# SCH_Controller_EasyEDA.net
KiCad netlist of a schematic drawn in EasyEDA
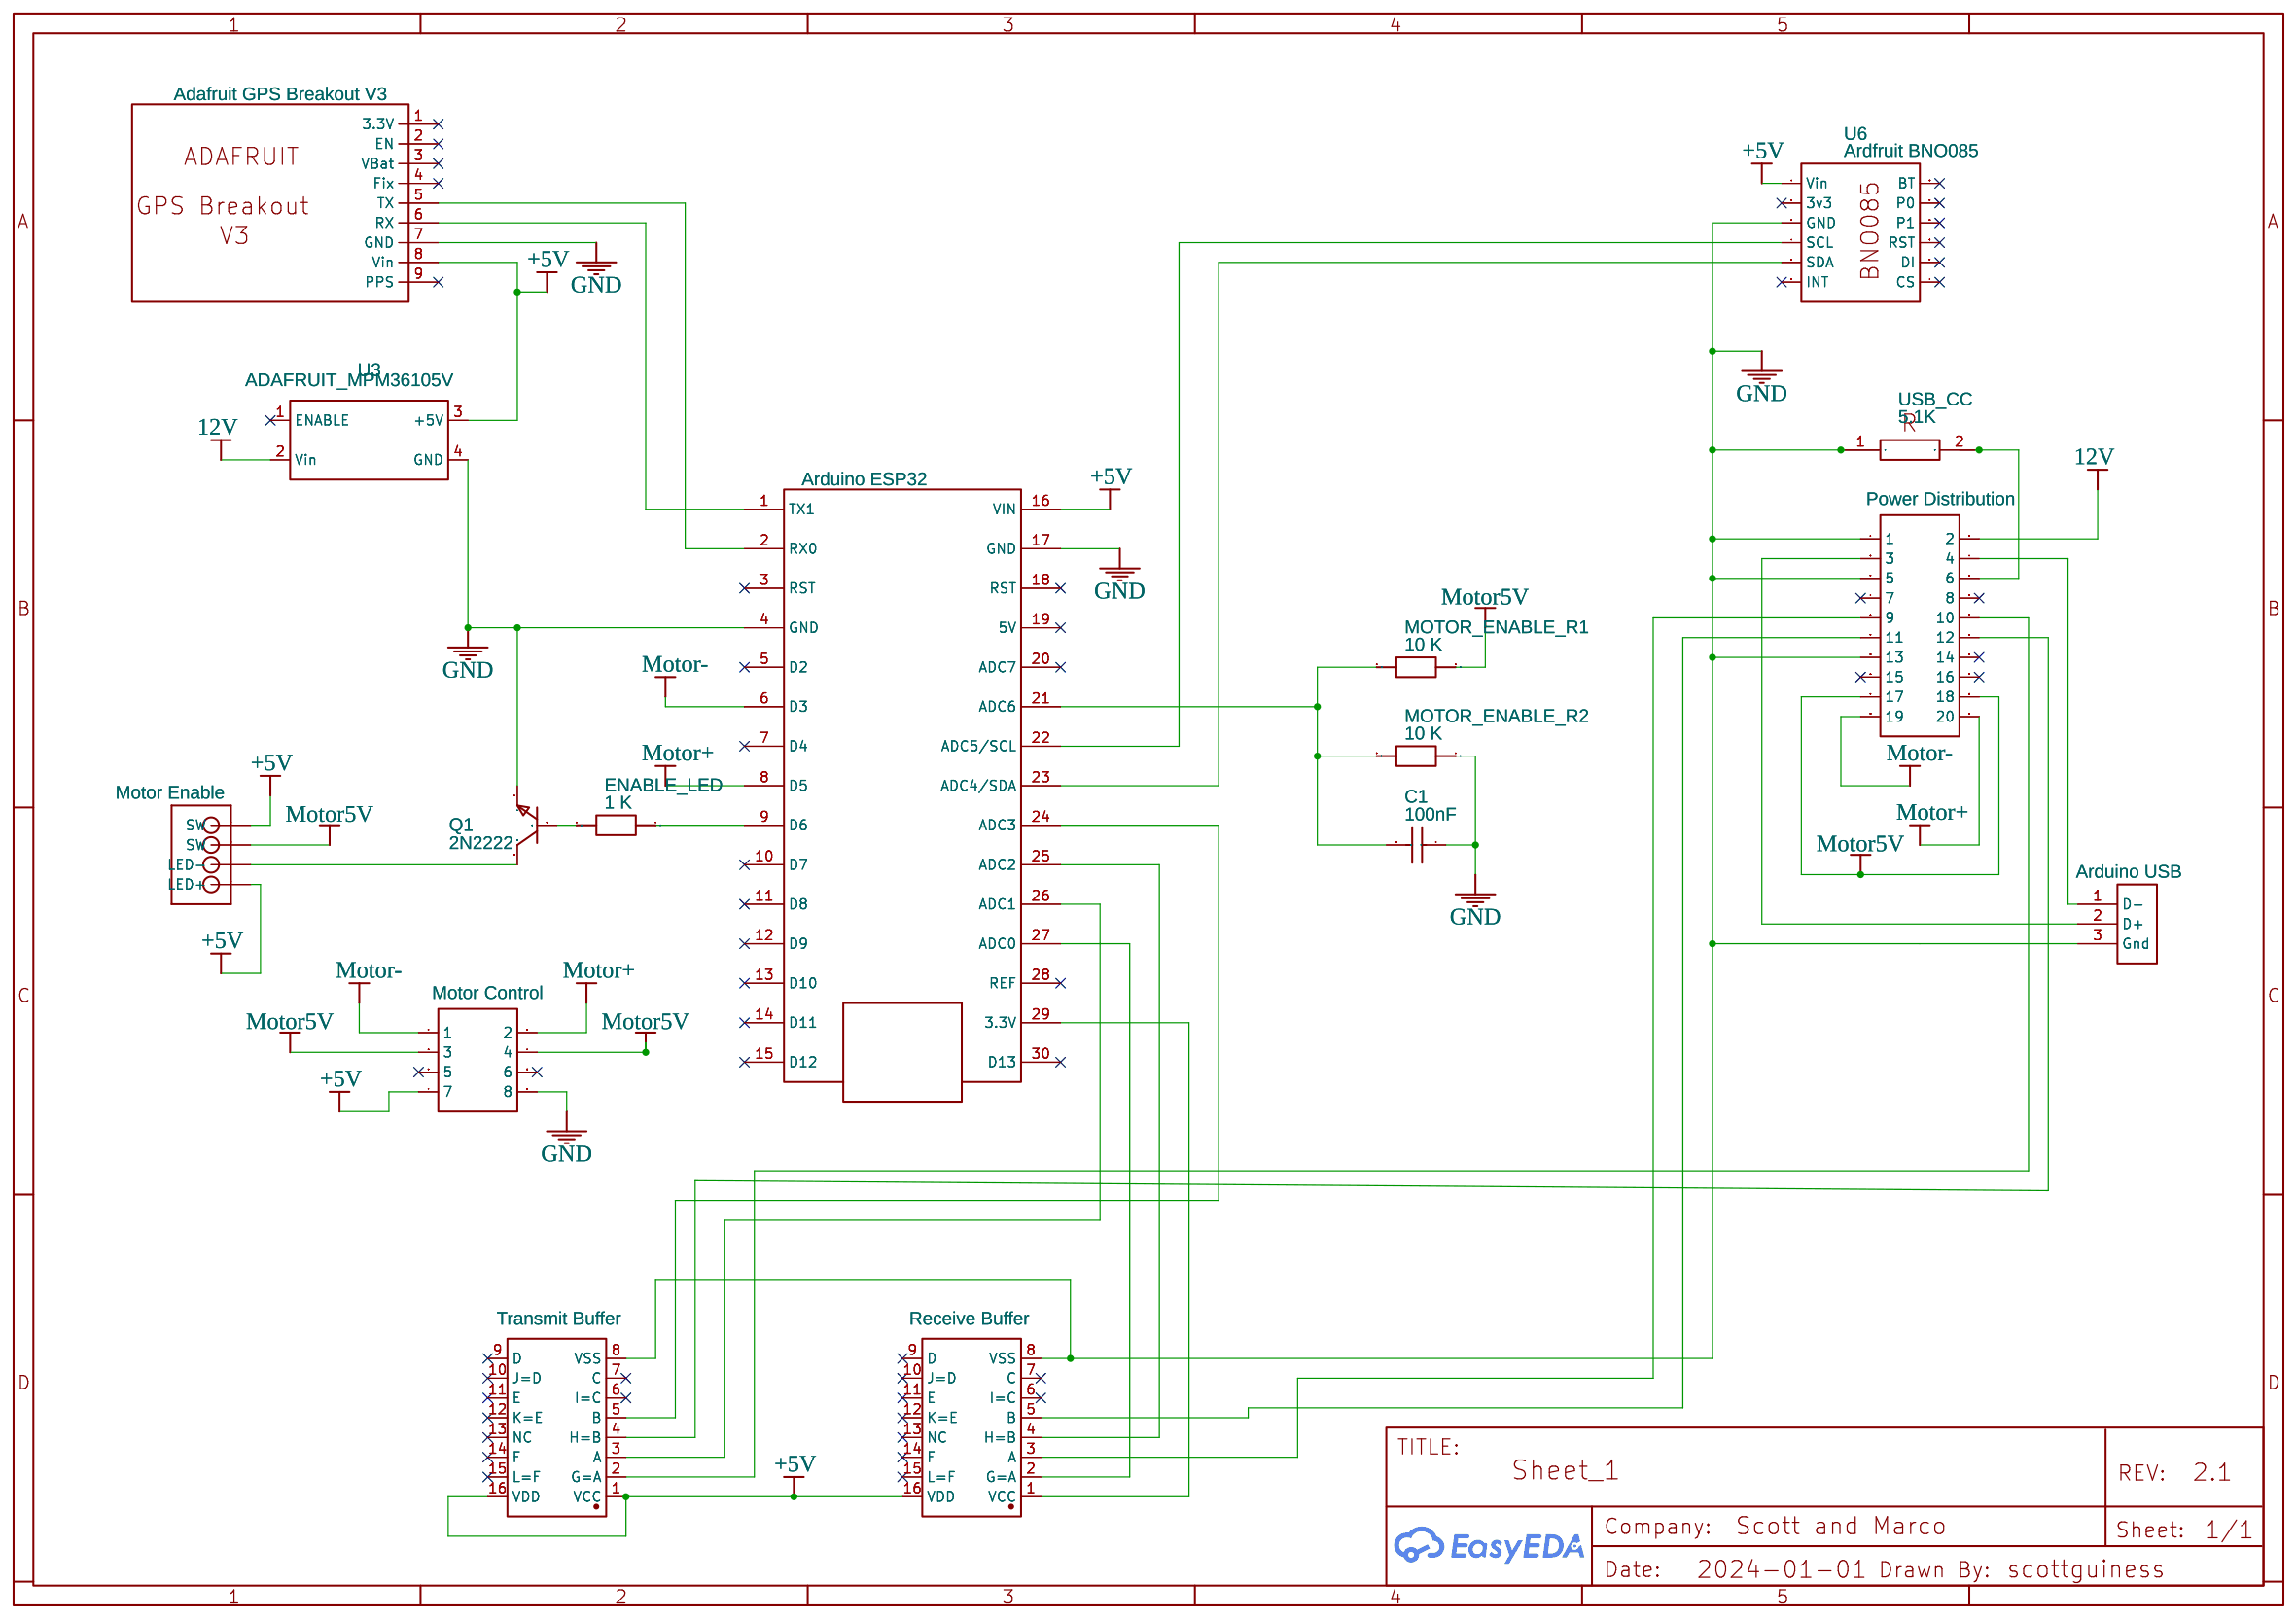
[diagram p0: schematic sheet]

(export (version "E")
  (design (tool "Eeschema 10.0.6"))
  (components
    (comp (ref "C1")
      (value "100nF")
      (fields (field (name "Manufacturer Part") "Capacitor_Ceramic"))
      (libsource (lib "") (part "Capacitor_Ceramic"))
    )
    (comp (ref "ENABLE_LED") (value "1 K") (libsource (lib "") (part "1 K 0.25w_1")))
    (comp (ref "HDR-M-2.54_2X4") (value "Motor Control") (libsource (lib "") (part "HDR-M-2.54_2x4")))
    (comp (ref "JST_XH_1X3") (value "Arduino USB") (libsource (lib "") (part "JST XH 1x3")))
    (comp (ref "MOTOR_ENABLE_R1") (value "10 K") (libsource (lib "") (part "1 K 0.25w")))
    (comp (ref "MOTOR_ENABLE_R2") (value "10 K") (libsource (lib "") (part "1 K 0.25w")))
    (comp (ref "POWER1") (value "Power Distribution") (libsource (lib "") (part "HDR-M-2.54_2x10")))
    (comp (ref "Q1")
      (value "2N2222")
      (fields (field (name "Manufacturer Part") "2N2222A") (field (name "Manufacturer") "ST(先科)"))
      (libsource (lib "") (part "2N2222"))
    )
    (comp (ref "U1") (value "Arduino ESP32") (libsource (lib "") (part "ARDUINO_NANO_R3")))
    (comp (ref "U2")
      (value "Receive Buffer")
      (fields (field (name "Manufacturer Part") "CD4010BE") (field (name "Manufacturer") "TI(德州仪器)"))
      (libsource (lib "") (part "CD4010BE"))
    )
    (comp (ref "U3") (value "ADAFRUIT_MPM36105V") (libsource (lib "") (part "ADAFRUIT_MPM36105V")))
    (comp (ref "U4")
      (value "Adafruit GPS Breakout V3")
      (fields (field (name "Manufacturer Part") "New SchematicLib"))
      (libsource (lib "") (part "Adafruit GPS Breakout V3"))
    )
    (comp (ref "U5")
      (value "Transmit Buffer")
      (fields (field (name "Manufacturer Part") "CD4010BE") (field (name "Manufacturer") "TI(德州仪器)"))
      (libsource (lib "") (part "CD4010BE"))
    )
    (comp (ref "U6")
      (value "Ardfruit BNO085")
      (fields (field (name "Manufacturer") "Ardfruit"))
      (libsource (lib "") (part "Ardfruit BNO085"))
    )
    (comp (ref "U7") (value "Motor Enable") (libsource (lib "") (part "HEADER-1X4-2.54-JST-PH")))
    (comp (ref "USB_CC")
      (value "5.1K")
      (fields (field (name "Manufacturer Part") "4211R-13") (field (name "Manufacturer") "API Delevan"))
      (libsource (lib "") (part "0.5W Resistor"))
    )
  )
  (nets
    (net (code "1") (name "+5V") (class "Default")
      (node (ref "HDR-M-2.54_2X4") (pin "7") (pinfunction "7_7") (pintype "unspecified"))
      (node (ref "U1") (pin "16") (pinfunction "VIN_16") (pintype "unspecified"))
      (node (ref "U2") (pin "16") (pinfunction "VDD_16") (pintype "unspecified"))
      (node (ref "U3") (pin "3") (pinfunction "+5V_3") (pintype "unspecified"))
      (node (ref "U4") (pin "8") (pinfunction "Vin_8") (pintype "unspecified"))
      (node (ref "U5") (pin "1") (pinfunction "VCC_1") (pintype "unspecified"))
      (node (ref "U5") (pin "16") (pinfunction "VDD_16") (pintype "unspecified"))
      (node (ref "U6") (pin "1") (pinfunction "Vin_1") (pintype "unspecified"))
      (node (ref "U7") (pin "P1") (pinfunction "SW_P1") (pintype "unspecified"))
      (node (ref "U7") (pin "P4") (pinfunction "LED+_P4") (pintype "unspecified"))
    )
    (net (code "2") (name "12V") (class "Default")
      (node (ref "POWER1") (pin "2") (pinfunction "2_2") (pintype "unspecified"))
      (node (ref "U3") (pin "2") (pinfunction "Vin_2") (pintype "unspecified"))
    )
    (net (code "3") (name "GND") (class "Default")
      (node (ref "C1") (pin "1") (pinfunction "1_1") (pintype "unspecified"))
      (node (ref "HDR-M-2.54_2X4") (pin "8") (pinfunction "8_8") (pintype "unspecified"))
      (node (ref "JST_XH_1X3") (pin "3") (pinfunction "Gnd_3") (pintype "unspecified"))
      (node (ref "MOTOR_ENABLE_R2") (pin "1") (pinfunction "1_1") (pintype "unspecified"))
      (node (ref "POWER1") (pin "1") (pinfunction "1_1") (pintype "unspecified"))
      (node (ref "POWER1") (pin "13") (pinfunction "13_13") (pintype "unspecified"))
      (node (ref "POWER1") (pin "5") (pinfunction "5_5") (pintype "unspecified"))
      (node (ref "Q1") (pin "1") (pinfunction "E_1") (pintype "unspecified"))
      (node (ref "U1") (pin "17") (pinfunction "GND_17") (pintype "unspecified"))
      (node (ref "U1") (pin "4") (pinfunction "GND_4") (pintype "unspecified"))
      (node (ref "U2") (pin "8") (pinfunction "VSS_8") (pintype "unspecified"))
      (node (ref "U3") (pin "4") (pinfunction "GND_4") (pintype "unspecified"))
      (node (ref "U4") (pin "7") (pinfunction "GND_7") (pintype "unspecified"))
      (node (ref "U5") (pin "8") (pinfunction "VSS_8") (pintype "unspecified"))
      (node (ref "U6") (pin "3") (pinfunction "GND_3") (pintype "unspecified"))
      (node (ref "USB_CC") (pin "1") (pinfunction "1_1") (pintype "unspecified"))
    )
    (net (code "4") (name "Motor+") (class "Default")
      (node (ref "HDR-M-2.54_2X4") (pin "2") (pinfunction "2_2") (pintype "unspecified"))
      (node (ref "POWER1") (pin "20") (pinfunction "20_20") (pintype "unspecified"))
      (node (ref "U1") (pin "8") (pinfunction "D5_8") (pintype "unspecified"))
    )
    (net (code "5") (name "Motor-") (class "Default")
      (node (ref "HDR-M-2.54_2X4") (pin "1") (pinfunction "1_1") (pintype "unspecified"))
      (node (ref "POWER1") (pin "19") (pinfunction "19_19") (pintype "unspecified"))
      (node (ref "U1") (pin "6") (pinfunction "D3_6") (pintype "unspecified"))
    )
    (net (code "6") (name "Motor5V") (class "Default")
      (node (ref "HDR-M-2.54_2X4") (pin "3") (pinfunction "3_3") (pintype "unspecified"))
      (node (ref "HDR-M-2.54_2X4") (pin "4") (pinfunction "4_4") (pintype "unspecified"))
      (node (ref "MOTOR_ENABLE_R1") (pin "1") (pinfunction "1_1") (pintype "unspecified"))
      (node (ref "POWER1") (pin "17") (pinfunction "17_17") (pintype "unspecified"))
      (node (ref "POWER1") (pin "18") (pinfunction "18_18") (pintype "unspecified"))
      (node (ref "U7") (pin "P2") (pinfunction "SW_P2") (pintype "unspecified"))
    )
    (net (code "7") (name "Net-(JST_XH_1X3-D+)") (class "Default")
      (node (ref "JST_XH_1X3") (pin "2") (pinfunction "D+_2") (pintype "unspecified"))
      (node (ref "POWER1") (pin "3") (pinfunction "3_3") (pintype "unspecified"))
    )
    (net (code "8") (name "Net-(JST_XH_1X3-D-)") (class "Default")
      (node (ref "JST_XH_1X3") (pin "1") (pinfunction "D-_1") (pintype "unspecified"))
      (node (ref "POWER1") (pin "4") (pinfunction "4_4") (pintype "unspecified"))
    )
    (net (code "9") (name "Net-(POWER1-Pad6)") (class "Default")
      (node (ref "POWER1") (pin "6") (pinfunction "6_6") (pintype "unspecified"))
      (node (ref "USB_CC") (pin "2") (pinfunction "2_2") (pintype "unspecified"))
    )
    (net (code "10") (name "Net-(Q1-B)") (class "Default")
      (node (ref "ENABLE_LED") (pin "2") (pinfunction "2_2") (pintype "unspecified"))
      (node (ref "Q1") (pin "2") (pinfunction "B_2") (pintype "unspecified"))
    )
    (net (code "11") (name "Net-(Q1-C)") (class "Default")
      (node (ref "Q1") (pin "3") (pinfunction "C_3") (pintype "unspecified"))
      (node (ref "U7") (pin "P3") (pinfunction "LED-_P3") (pintype "unspecified"))
    )
    (net (code "12") (name "Net-(U1-3.3V)") (class "Default")
      (node (ref "U1") (pin "29") (pinfunction "3.3V_29") (pintype "unspecified"))
      (node (ref "U2") (pin "1") (pinfunction "VCC_1") (pintype "unspecified"))
    )
    (net (code "13") (name "Net-(U1-ADC0)") (class "Default")
      (node (ref "U1") (pin "27") (pinfunction "ADC0_27") (pintype "unspecified"))
      (node (ref "U2") (pin "2") (pinfunction "G=A_2") (pintype "unspecified"))
    )
    (net (code "14") (name "Net-(U1-ADC1)") (class "Default")
      (node (ref "U1") (pin "26") (pinfunction "ADC1_26") (pintype "unspecified"))
      (node (ref "U5") (pin "3") (pinfunction "A_3") (pintype "unspecified"))
    )
    (net (code "15") (name "Net-(U1-ADC2)") (class "Default")
      (node (ref "U1") (pin "25") (pinfunction "ADC2_25") (pintype "unspecified"))
      (node (ref "U2") (pin "4") (pinfunction "H=B_4") (pintype "unspecified"))
    )
    (net (code "16") (name "Net-(U1-ADC3)") (class "Default")
      (node (ref "U1") (pin "24") (pinfunction "ADC3_24") (pintype "unspecified"))
      (node (ref "U5") (pin "5") (pinfunction "B_5") (pintype "unspecified"))
    )
    (net (code "17") (name "Net-(U1-ADC4{slash}SDA)") (class "Default")
      (node (ref "U1") (pin "23") (pinfunction "ADC4/SDA_23") (pintype "unspecified"))
      (node (ref "U6") (pin "5") (pinfunction "SDA_5") (pintype "unspecified"))
    )
    (net (code "18") (name "Net-(U1-ADC5{slash}SCL)") (class "Default")
      (node (ref "U1") (pin "22") (pinfunction "ADC5/SCL_22") (pintype "unspecified"))
      (node (ref "U6") (pin "4") (pinfunction "SCL_4") (pintype "unspecified"))
    )
    (net (code "19") (name "Net-(U1-ADC6)") (class "Default")
      (node (ref "C1") (pin "2") (pinfunction "2_2") (pintype "unspecified"))
      (node (ref "MOTOR_ENABLE_R1") (pin "2") (pinfunction "2_2") (pintype "unspecified"))
      (node (ref "MOTOR_ENABLE_R2") (pin "2") (pinfunction "2_2") (pintype "unspecified"))
      (node (ref "U1") (pin "21") (pinfunction "ADC6_21") (pintype "unspecified"))
    )
    (net (code "20") (name "Net-(U1-D6)") (class "Default")
      (node (ref "ENABLE_LED") (pin "1") (pinfunction "1_1") (pintype "unspecified"))
      (node (ref "U1") (pin "9") (pinfunction "D6_9") (pintype "unspecified"))
    )
    (net (code "21") (name "Net-(U1-RX0)") (class "Default")
      (node (ref "U1") (pin "2") (pinfunction "RX0_2") (pintype "unspecified"))
      (node (ref "U4") (pin "5") (pinfunction "TX_5") (pintype "unspecified"))
    )
    (net (code "22") (name "Net-(U1-TX1)") (class "Default")
      (node (ref "U1") (pin "1") (pinfunction "TX1_1") (pintype "unspecified"))
      (node (ref "U4") (pin "6") (pinfunction "RX_6") (pintype "unspecified"))
    )
    (net (code "23") (name "Net-(U2-A)") (class "Default")
      (node (ref "POWER1") (pin "9") (pinfunction "9_9") (pintype "unspecified"))
      (node (ref "U2") (pin "3") (pinfunction "A_3") (pintype "unspecified"))
    )
    (net (code "24") (name "Net-(U2-B)") (class "Default")
      (node (ref "POWER1") (pin "11") (pinfunction "11_11") (pintype "unspecified"))
      (node (ref "U2") (pin "5") (pinfunction "B_5") (pintype "unspecified"))
    )
    (net (code "25") (name "Net-(U5-G=A)") (class "Default")
      (node (ref "POWER1") (pin "10") (pinfunction "10_10") (pintype "unspecified"))
      (node (ref "U5") (pin "2") (pinfunction "G=A_2") (pintype "unspecified"))
    )
    (net (code "26") (name "Net-(U5-H=B)") (class "Default")
      (node (ref "POWER1") (pin "12") (pinfunction "12_12") (pintype "unspecified"))
      (node (ref "U5") (pin "4") (pinfunction "H=B_4") (pintype "unspecified"))
    )
    (net (code "27") (name "unconnected-(HDR-M-2.54_2X4-Pad5)") (class "Default")
      (node (ref "HDR-M-2.54_2X4") (pin "5") (pinfunction "5_5") (pintype "unspecified+no_connect"))
    )
    (net (code "28") (name "unconnected-(HDR-M-2.54_2X4-Pad6)") (class "Default")
      (node (ref "HDR-M-2.54_2X4") (pin "6") (pinfunction "6_6") (pintype "unspecified+no_connect"))
    )
    (net (code "29") (name "unconnected-(POWER1-Pad7)") (class "Default")
      (node (ref "POWER1") (pin "7") (pinfunction "7_7") (pintype "unspecified+no_connect"))
    )
    (net (code "30") (name "unconnected-(POWER1-Pad8)") (class "Default")
      (node (ref "POWER1") (pin "8") (pinfunction "8_8") (pintype "unspecified+no_connect"))
    )
    (net (code "31") (name "unconnected-(POWER1-Pad14)") (class "Default")
      (node (ref "POWER1") (pin "14") (pinfunction "14_14") (pintype "unspecified+no_connect"))
    )
    (net (code "32") (name "unconnected-(POWER1-Pad15)") (class "Default")
      (node (ref "POWER1") (pin "15") (pinfunction "15_15") (pintype "unspecified+no_connect"))
    )
    (net (code "33") (name "unconnected-(POWER1-Pad16)") (class "Default")
      (node (ref "POWER1") (pin "16") (pinfunction "16_16") (pintype "unspecified+no_connect"))
    )
    (net (code "34") (name "unconnected-(U1-5V-Pad19)") (class "Default")
      (node (ref "U1") (pin "19") (pinfunction "5V_19") (pintype "unspecified+no_connect"))
    )
    (net (code "35") (name "unconnected-(U1-ADC7-Pad20)") (class "Default")
      (node (ref "U1") (pin "20") (pinfunction "ADC7_20") (pintype "unspecified+no_connect"))
    )
    (net (code "36") (name "unconnected-(U1-D2-Pad5)") (class "Default")
      (node (ref "U1") (pin "5") (pinfunction "D2_5") (pintype "unspecified+no_connect"))
    )
    (net (code "37") (name "unconnected-(U1-D4-Pad7)") (class "Default")
      (node (ref "U1") (pin "7") (pinfunction "D4_7") (pintype "unspecified+no_connect"))
    )
    (net (code "38") (name "unconnected-(U1-D7-Pad10)") (class "Default")
      (node (ref "U1") (pin "10") (pinfunction "D7_10") (pintype "unspecified+no_connect"))
    )
    (net (code "39") (name "unconnected-(U1-D8-Pad11)") (class "Default")
      (node (ref "U1") (pin "11") (pinfunction "D8_11") (pintype "unspecified+no_connect"))
    )
    (net (code "40") (name "unconnected-(U1-D9-Pad12)") (class "Default")
      (node (ref "U1") (pin "12") (pinfunction "D9_12") (pintype "unspecified+no_connect"))
    )
    (net (code "41") (name "unconnected-(U1-D10-Pad13)") (class "Default")
      (node (ref "U1") (pin "13") (pinfunction "D10_13") (pintype "unspecified+no_connect"))
    )
    (net (code "42") (name "unconnected-(U1-D11-Pad14)") (class "Default")
      (node (ref "U1") (pin "14") (pinfunction "D11_14") (pintype "unspecified+no_connect"))
    )
    (net (code "43") (name "unconnected-(U1-D12-Pad15)") (class "Default")
      (node (ref "U1") (pin "15") (pinfunction "D12_15") (pintype "unspecified+no_connect"))
    )
    (net (code "44") (name "unconnected-(U1-D13-Pad30)") (class "Default")
      (node (ref "U1") (pin "30") (pinfunction "D13_30") (pintype "unspecified+no_connect"))
    )
    (net (code "45") (name "unconnected-(U1-REF-Pad28)") (class "Default")
      (node (ref "U1") (pin "28") (pinfunction "REF_28") (pintype "unspecified+no_connect"))
    )
    (net (code "46") (name "unconnected-(U1-RST-Pad3)") (class "Default")
      (node (ref "U1") (pin "3") (pinfunction "RST_3") (pintype "unspecified+no_connect"))
    )
    (net (code "47") (name "unconnected-(U1-RST-Pad18)") (class "Default")
      (node (ref "U1") (pin "18") (pinfunction "RST_18") (pintype "unspecified+no_connect"))
    )
    (net (code "48") (name "unconnected-(U2-C-Pad7)") (class "Default")
      (node (ref "U2") (pin "7") (pinfunction "C_7") (pintype "unspecified+no_connect"))
    )
    (net (code "49") (name "unconnected-(U2-D-Pad9)") (class "Default")
      (node (ref "U2") (pin "9") (pinfunction "D_9") (pintype "unspecified+no_connect"))
    )
    (net (code "50") (name "unconnected-(U2-E-Pad11)") (class "Default")
      (node (ref "U2") (pin "11") (pinfunction "E_11") (pintype "unspecified+no_connect"))
    )
    (net (code "51") (name "unconnected-(U2-F-Pad14)") (class "Default")
      (node (ref "U2") (pin "14") (pinfunction "F_14") (pintype "unspecified+no_connect"))
    )
    (net (code "52") (name "unconnected-(U2-I=C-Pad6)") (class "Default")
      (node (ref "U2") (pin "6") (pinfunction "I=C_6") (pintype "unspecified+no_connect"))
    )
    (net (code "53") (name "unconnected-(U2-J=D-Pad10)") (class "Default")
      (node (ref "U2") (pin "10") (pinfunction "J=D_10") (pintype "unspecified+no_connect"))
    )
    (net (code "54") (name "unconnected-(U2-K=E-Pad12)") (class "Default")
      (node (ref "U2") (pin "12") (pinfunction "K=E_12") (pintype "unspecified+no_connect"))
    )
    (net (code "55") (name "unconnected-(U2-L=F-Pad15)") (class "Default")
      (node (ref "U2") (pin "15") (pinfunction "L=F_15") (pintype "unspecified+no_connect"))
    )
    (net (code "56") (name "unconnected-(U2-NC-Pad13)") (class "Default")
      (node (ref "U2") (pin "13") (pinfunction "NC_13") (pintype "unspecified+no_connect"))
    )
    (net (code "57") (name "unconnected-(U3-ENABLE-Pad1)") (class "Default")
      (node (ref "U3") (pin "1") (pinfunction "ENABLE_1") (pintype "unspecified+no_connect"))
    )
    (net (code "58") (name "unconnected-(U4-3.3V-Pad1)") (class "Default")
      (node (ref "U4") (pin "1") (pinfunction "3.3V_1") (pintype "unspecified+no_connect"))
    )
    (net (code "59") (name "unconnected-(U4-EN-Pad2)") (class "Default")
      (node (ref "U4") (pin "2") (pinfunction "EN_2") (pintype "unspecified+no_connect"))
    )
    (net (code "60") (name "unconnected-(U4-Fix-Pad4)") (class "Default")
      (node (ref "U4") (pin "4") (pinfunction "Fix_4") (pintype "unspecified+no_connect"))
    )
    (net (code "61") (name "unconnected-(U4-PPS-Pad9)") (class "Default")
      (node (ref "U4") (pin "9") (pinfunction "PPS_9") (pintype "unspecified+no_connect"))
    )
    (net (code "62") (name "unconnected-(U4-VBat-Pad3)") (class "Default")
      (node (ref "U4") (pin "3") (pinfunction "VBat_3") (pintype "unspecified+no_connect"))
    )
    (net (code "63") (name "unconnected-(U5-C-Pad7)") (class "Default")
      (node (ref "U5") (pin "7") (pinfunction "C_7") (pintype "unspecified+no_connect"))
    )
    (net (code "64") (name "unconnected-(U5-D-Pad9)") (class "Default")
      (node (ref "U5") (pin "9") (pinfunction "D_9") (pintype "unspecified+no_connect"))
    )
    (net (code "65") (name "unconnected-(U5-E-Pad11)") (class "Default")
      (node (ref "U5") (pin "11") (pinfunction "E_11") (pintype "unspecified+no_connect"))
    )
    (net (code "66") (name "unconnected-(U5-F-Pad14)") (class "Default")
      (node (ref "U5") (pin "14") (pinfunction "F_14") (pintype "unspecified+no_connect"))
    )
    (net (code "67") (name "unconnected-(U5-I=C-Pad6)") (class "Default")
      (node (ref "U5") (pin "6") (pinfunction "I=C_6") (pintype "unspecified+no_connect"))
    )
    (net (code "68") (name "unconnected-(U5-J=D-Pad10)") (class "Default")
      (node (ref "U5") (pin "10") (pinfunction "J=D_10") (pintype "unspecified+no_connect"))
    )
    (net (code "69") (name "unconnected-(U5-K=E-Pad12)") (class "Default")
      (node (ref "U5") (pin "12") (pinfunction "K=E_12") (pintype "unspecified+no_connect"))
    )
    (net (code "70") (name "unconnected-(U5-L=F-Pad15)") (class "Default")
      (node (ref "U5") (pin "15") (pinfunction "L=F_15") (pintype "unspecified+no_connect"))
    )
    (net (code "71") (name "unconnected-(U5-NC-Pad13)") (class "Default")
      (node (ref "U5") (pin "13") (pinfunction "NC_13") (pintype "unspecified+no_connect"))
    )
    (net (code "72") (name "unconnected-(U6-3v3-Pad2)") (class "Default")
      (node (ref "U6") (pin "2") (pinfunction "3v3_2") (pintype "unspecified+no_connect"))
    )
    (net (code "73") (name "unconnected-(U6-BT-Pad12)") (class "Default")
      (node (ref "U6") (pin "12") (pinfunction "BT_12") (pintype "unspecified+no_connect"))
    )
    (net (code "74") (name "unconnected-(U6-CS-Pad7)") (class "Default")
      (node (ref "U6") (pin "7") (pinfunction "CS_7") (pintype "unspecified+no_connect"))
    )
    (net (code "75") (name "unconnected-(U6-DI-Pad8)") (class "Default")
      (node (ref "U6") (pin "8") (pinfunction "DI_8") (pintype "unspecified+no_connect"))
    )
    (net (code "76") (name "unconnected-(U6-INT-Pad6)") (class "Default")
      (node (ref "U6") (pin "6") (pinfunction "INT_6") (pintype "unspecified+no_connect"))
    )
    (net (code "77") (name "unconnected-(U6-P0-Pad11)") (class "Default")
      (node (ref "U6") (pin "11") (pinfunction "P0_11") (pintype "unspecified+no_connect"))
    )
    (net (code "78") (name "unconnected-(U6-P1-Pad10)") (class "Default")
      (node (ref "U6") (pin "10") (pinfunction "P1_10") (pintype "unspecified+no_connect"))
    )
    (net (code "79") (name "unconnected-(U6-RST-Pad9)") (class "Default")
      (node (ref "U6") (pin "9") (pinfunction "RST_9") (pintype "unspecified+no_connect"))
    )
  )
)
